# emag.net
KiCad netlist of a schematic drawn in Altium Designer
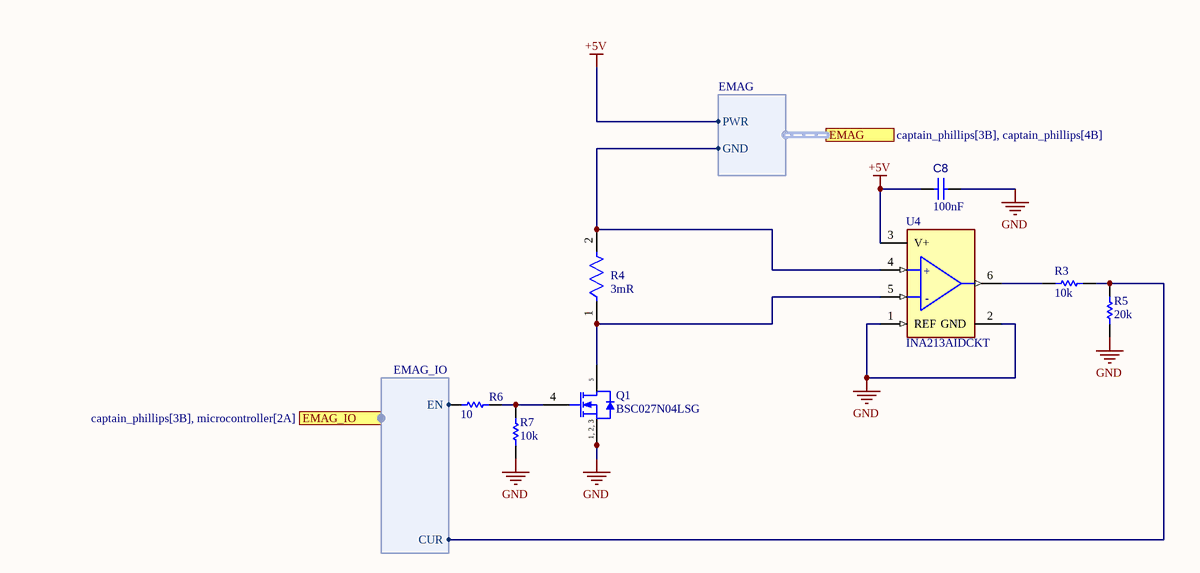
[diagram p0: emag.SchDoc]

(export (version "E")
  (design (tool "Eeschema 10.0.6"))
  (components
    (comp (ref "C8")
      (value "100nF")
      (footprint "3")
      (description "CAP CER 100 nF 50V X7R 0603")
      (fields (field (name "TOLERANCE") "10%") (field (name "LCSC PART NUMBER") "C14663"))
      (libsource (lib "Dalhousie Formula SAE") (part "CAP-NP-2"))
    )
    (comp (ref "Q1")
      (value "BSC027N04LSG")
      (footprint "INF-PG-TDSON-8-1_V")
      (fields (field (name "LCSC PART NUMBER") "C2802513"))
      (libsource (lib "Dalhousie Formula SAE") (part "INF-NEMOS-SSSGDDDD-8"))
    )
    (comp (ref "R3")
      (value "10k")
      (footprint "RESC1608X55X25ML10T15")
      (description "0603 (1608 Metric) 1/10 W 10K 1 Thick Film Chip Resistor")
      (fields (field (name "POWER") "100mW") (field (name "LCSC PART NUMBER") "C25804"))
      (libsource (lib "Dalhousie Formula SAE") (part "RES-2"))
    )
    (comp (ref "R4")
      (value "CRE2512-FZ-R003E-3")
      (footprint "FP-CRE2512-R001-R004-MFG")
      (description "RES 0.003 OHM 1% 3W 2512")
      (fields (field (name "TOLERANCE") "1%") (field (name "RESISTANCE") "3mR"))
      (libsource (lib "Altium Content Vault") (part "1029c3af85768c4190bb7ad29bc67b5"))
    )
    (comp (ref "R5")
      (value "20k")
      (footprint "RESC1608X55X25ML10T15")
      (description "0603 (1608 Metric) 1/10 W 20K 1 Thick Film Chip Resistor")
      (fields (field (name "TOLERANCE") "1%") (field (name "LCSC PART NUMBER") "C4184"))
      (libsource (lib "Dalhousie Formula SAE") (part "RES-2"))
    )
    (comp (ref "R6")
      (value "10")
      (footprint "RESC1608X55X25ML10T15")
      (description "0603 (1608 Metric) 1/10 W 10R 1 Thick Film Chip Resistor")
      (fields (field (name "POWER") "100mW") (field (name "TOLERANCE") "1%"))
      (libsource (lib "Dalhousie Formula SAE") (part "RES-2"))
    )
    (comp (ref "R7")
      (value "10k")
      (footprint "RESC1608X55X25ML10T15")
      (description "0603 (1608 Metric) 1/10 W 10K 1 Thick Film Chip Resistor")
      (fields (field (name "POWER") "100mW") (field (name "LCSC PART NUMBER") "C25804"))
      (libsource (lib "Dalhousie Formula SAE") (part "RES-2"))
    )
    (comp (ref "U4")
      (value "INA213AIDCKT")
      (footprint "FP-DCK0006A-MFG")
      (description "Operational Amplifier, 1 Func, PDSO6")
      (libsource (lib "Dalhousie Formula SAE") (part "9e0f38de031fe9615e73145e91d432c"))
    )
  )
  (nets
    (net (code "3") (name "+5V") (class "Default")
      (node (ref "C8") (pin "1") (pinfunction "1_1") (pintype "passive"))
      (node (ref "U4") (pin "3") (pinfunction "V+_3") (pintype "power_in"))
    )
    (net (code "4") (name "/CUR") (class "Default")
      (node (ref "R3") (pin "1") (pinfunction "1_1") (pintype "passive"))
      (node (ref "R5") (pin "2") (pinfunction "2_2") (pintype "passive"))
    )
    (net (code "5") (name "/EN") (class "Default")
      (node (ref "R6") (pin "1") (pinfunction "1_1") (pintype "passive"))
    )
    (net (code "8") (name "GND") (class "Default")
      (node (ref "C8") (pin "2") (pinfunction "2_2") (pintype "passive"))
      (node (ref "Q1") (pin "1") (pinfunction "SOURCE_1") (pintype "passive"))
      (node (ref "Q1") (pin "2") (pinfunction "SOURCE_2") (pintype "passive"))
      (node (ref "Q1") (pin "3") (pinfunction "SOURCE_3") (pintype "passive"))
      (node (ref "R5") (pin "1") (pinfunction "1_1") (pintype "passive"))
      (node (ref "R7") (pin "1") (pinfunction "1_1") (pintype "passive"))
      (node (ref "U4") (pin "1") (pinfunction "REF_1") (pintype "input"))
      (node (ref "U4") (pin "2") (pinfunction "GND_2") (pintype "power_in"))
    )
    (net (code "9") (name "Net-(Q1-DRAIN)") (class "Default")
      (node (ref "Q1") (pin "5") (pinfunction "DRAIN_5") (pintype "passive"))
      (node (ref "R4") (pin "1") (pinfunction "1_1") (pintype "passive"))
      (node (ref "U4") (pin "5") (pinfunction "IN-_5") (pintype "input"))
    )
    (net (code "10") (name "Net-(Q1-GATE)") (class "Default")
      (node (ref "Q1") (pin "4") (pinfunction "GATE_4") (pintype "passive"))
      (node (ref "R6") (pin "2") (pinfunction "2_2") (pintype "passive"))
      (node (ref "R7") (pin "2") (pinfunction "2_2") (pintype "passive"))
    )
    (net (code "11") (name "Net-(U4-IN+)") (class "Default")
      (node (ref "R4") (pin "2") (pinfunction "2_2") (pintype "passive"))
      (node (ref "U4") (pin "4") (pinfunction "IN+_4") (pintype "input"))
    )
    (net (code "12") (name "Net-(U4-OUT)") (class "Default")
      (node (ref "R3") (pin "2") (pinfunction "2_2") (pintype "passive"))
      (node (ref "U4") (pin "6") (pinfunction "OUT_6") (pintype "output"))
    )
  )
)
